# Connectors_ASCII.net
KiCad netlist of a schematic drawn in Altium Designer
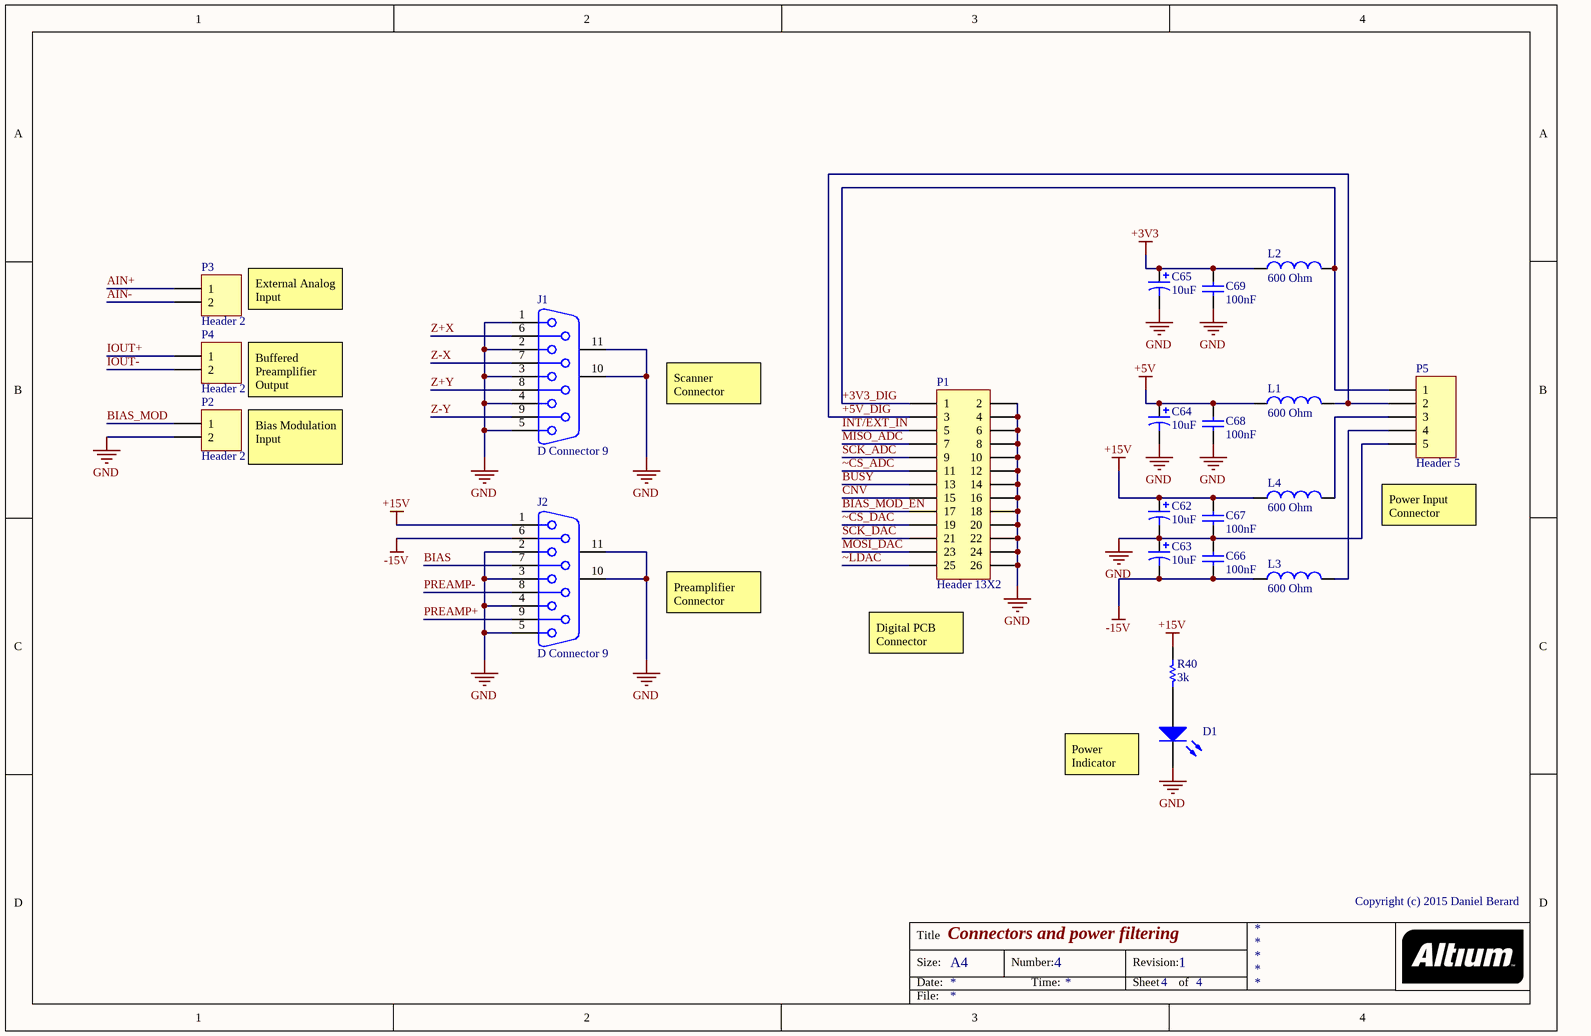
[diagram p0: Connectors_ASCII.SchDoc]

(export (version "E")
  (design (tool "Eeschema 10.0.6"))
  (components
    (comp (ref "C62")
      (value "10uF")
      (footprint "3528")
      (description "Polarized Capacitor (Radial)")
      (fields (field (name "PUBLISHER") "Altium Limited"))
      (libsource (lib "Miscellaneous Devices") (part "Cap Pol1"))
    )
    (comp (ref "C63")
      (value "10uF")
      (footprint "3528")
      (description "Polarized Capacitor (Radial)")
      (fields (field (name "PUBLISHER") "Altium Limited"))
      (libsource (lib "Miscellaneous Devices") (part "Cap Pol1"))
    )
    (comp (ref "C64")
      (value "10uF")
      (footprint "6-0805_N")
      (description "Polarized Capacitor (Radial)")
      (fields (field (name "PUBLISHER") "Altium Limited"))
      (libsource (lib "Miscellaneous Devices") (part "Cap Pol1"))
    )
    (comp (ref "C65")
      (value "10uF")
      (footprint "6-0805_N")
      (description "Polarized Capacitor (Radial)")
      (fields (field (name "PUBLISHER") "Altium Limited"))
      (libsource (lib "Miscellaneous Devices") (part "Cap Pol1"))
    )
    (comp (ref "C66")
      (value "100nF")
      (footprint "6-0805_N")
      (description "Capacitor")
      (fields (field (name "PUBLISHER") "Altium Limited"))
      (libsource (lib "Miscellaneous Devices") (part "Cap"))
    )
    (comp (ref "C67")
      (value "100nF")
      (footprint "6-0805_N")
      (description "Capacitor")
      (fields (field (name "PUBLISHER") "Altium Limited"))
      (libsource (lib "Miscellaneous Devices") (part "Cap"))
    )
    (comp (ref "C68")
      (value "100nF")
      (footprint "6-0805_N")
      (description "Capacitor")
      (fields (field (name "PUBLISHER") "Altium Limited"))
      (libsource (lib "Miscellaneous Devices") (part "Cap"))
    )
    (comp (ref "C69")
      (value "100nF")
      (footprint "6-0805_N")
      (description "Capacitor")
      (fields (field (name "PUBLISHER") "Altium Limited"))
      (libsource (lib "Miscellaneous Devices") (part "Cap"))
    )
    (comp (ref "D1")
      (value "~")
      (footprint "6-0805_N")
      (description "Typical INFRARED GaAs LED")
      (fields (field (name "PUBLISHER") "Altium Limited"))
      (libsource (lib "Miscellaneous Devices") (part "LED0"))
    )
    (comp (ref "J1")
      (value "D Connector 9")
      (footprint "DSUB1.385-2H9")
      (description "Receptacle Assembly, 9 Position, Right Angle")
      (fields (field (name "PUBLISHER") "Altium Limited"))
      (libsource (lib "Miscellaneous Connectors") (part "D Connector 9"))
    )
    (comp (ref "J2")
      (value "D Connector 9")
      (footprint "DSUB1.385-2H9")
      (description "Receptacle Assembly, 9 Position, Right Angle")
      (fields (field (name "PUBLISHER") "Altium Limited"))
      (libsource (lib "Miscellaneous Connectors") (part "D Connector 9"))
    )
    (comp (ref "L1")
      (value "600 Ohm")
      (footprint "6-0805_N")
      (description "Inductor")
      (fields (field (name "PUBLISHER") "Altium Limited"))
      (libsource (lib "Miscellaneous Devices") (part "Inductor"))
    )
    (comp (ref "L2")
      (value "600 Ohm")
      (footprint "6-0805_N")
      (description "Inductor")
      (fields (field (name "PUBLISHER") "Altium Limited"))
      (libsource (lib "Miscellaneous Devices") (part "Inductor"))
    )
    (comp (ref "L3")
      (value "600 Ohm")
      (footprint "6-0805_N")
      (description "Inductor")
      (fields (field (name "PUBLISHER") "Altium Limited"))
      (libsource (lib "Miscellaneous Devices") (part "Inductor"))
    )
    (comp (ref "L4")
      (value "600 Ohm")
      (footprint "6-0805_N")
      (description "Inductor")
      (fields (field (name "PUBLISHER") "Altium Limited"))
      (libsource (lib "Miscellaneous Devices") (part "Inductor"))
    )
    (comp (ref "P1")
      (value "Header 13X2")
      (footprint "HDR2X13")
      (description "Header, 13-Pin, Dual row")
      (fields (field (name "PUBLISHER") "Altium Limited"))
      (libsource (lib "Miscellaneous Connectors") (part "Header 13X2"))
    )
    (comp (ref "P2")
      (value "Header 2")
      (footprint "HDR1X2")
      (description "Header, 2-Pin")
      (fields (field (name "PUBLISHER") "Altium Limited"))
      (libsource (lib "Miscellaneous Connectors") (part "Header 2"))
    )
    (comp (ref "P3")
      (value "Header 2")
      (footprint "HDR1X2")
      (description "Header, 2-Pin")
      (fields (field (name "PUBLISHER") "Altium Limited"))
      (libsource (lib "Miscellaneous Connectors") (part "Header 2"))
    )
    (comp (ref "P4")
      (value "Header 2")
      (footprint "HDR1X2")
      (description "Header, 2-Pin")
      (fields (field (name "PUBLISHER") "Altium Limited"))
      (libsource (lib "Miscellaneous Connectors") (part "Header 2"))
    )
    (comp (ref "P5")
      (value "Header 5")
      (footprint "HDR1X5")
      (description "Header, 5-Pin")
      (fields (field (name "PUBLISHER") "Altium Limited"))
      (libsource (lib "Miscellaneous Connectors") (part "Header 5"))
    )
    (comp (ref "R40")
      (value "3k")
      (footprint "6-0805_N")
      (description "Resistor")
      (fields (field (name "PUBLISHER") "Altium Limited"))
      (libsource (lib "Miscellaneous Devices") (part "Res1"))
    )
  )
  (nets
    (net (code "1") (name "+3V3") (class "Default")
      (node (ref "C65") (pin "1") (pinfunction "1_1") (pintype "passive"))
      (node (ref "C69") (pin "1") (pinfunction "1_1") (pintype "passive"))
      (node (ref "L2") (pin "1") (pinfunction "1_1") (pintype "passive"))
    )
    (net (code "2") (name "+5V") (class "Default")
      (node (ref "C64") (pin "1") (pinfunction "1_1") (pintype "passive"))
      (node (ref "C68") (pin "1") (pinfunction "1_1") (pintype "passive"))
      (node (ref "L1") (pin "1") (pinfunction "1_1") (pintype "passive"))
    )
    (net (code "3") (name "+15V") (class "Default")
      (node (ref "C62") (pin "1") (pinfunction "1_1") (pintype "passive"))
      (node (ref "C67") (pin "1") (pinfunction "1_1") (pintype "passive"))
      (node (ref "J2") (pin "1") (pinfunction "1_1") (pintype "passive"))
      (node (ref "L4") (pin "1") (pinfunction "1_1") (pintype "passive"))
      (node (ref "R40") (pin "2") (pinfunction "2_2") (pintype "passive"))
    )
    (net (code "4") (name "-15V") (class "Default")
      (node (ref "C63") (pin "2") (pinfunction "2_2") (pintype "passive"))
      (node (ref "C66") (pin "2") (pinfunction "2_2") (pintype "passive"))
      (node (ref "J2") (pin "6") (pinfunction "6_6") (pintype "passive"))
      (node (ref "L3") (pin "1") (pinfunction "1_1") (pintype "passive"))
    )
    (net (code "5") (name "/+3V3_DIG") (class "Default")
      (node (ref "L2") (pin "2") (pinfunction "2_2") (pintype "passive"))
      (node (ref "P1") (pin "1") (pinfunction "1_1") (pintype "passive"))
      (node (ref "P5") (pin "1") (pinfunction "1_1") (pintype "passive"))
    )
    (net (code "6") (name "/+5V_DIG") (class "Default")
      (node (ref "L1") (pin "2") (pinfunction "2_2") (pintype "passive"))
      (node (ref "P1") (pin "3") (pinfunction "3_3") (pintype "passive"))
      (node (ref "P5") (pin "2") (pinfunction "2_2") (pintype "passive"))
    )
    (net (code "7") (name "/AIN+") (class "Default")
      (node (ref "P3") (pin "1") (pinfunction "1_1") (pintype "passive"))
    )
    (net (code "8") (name "/AIN-") (class "Default")
      (node (ref "P3") (pin "2") (pinfunction "2_2") (pintype "passive"))
    )
    (net (code "9") (name "/BIAS") (class "Default")
      (node (ref "J2") (pin "7") (pinfunction "7_7") (pintype "passive"))
    )
    (net (code "10") (name "/BIAS_MOD") (class "Default")
      (node (ref "P2") (pin "1") (pinfunction "1_1") (pintype "passive"))
    )
    (net (code "11") (name "/BIAS_MOD_EN") (class "Default")
      (node (ref "P1") (pin "17") (pinfunction "17_17") (pintype "passive"))
    )
    (net (code "12") (name "/BUSY") (class "Default")
      (node (ref "P1") (pin "13") (pinfunction "13_13") (pintype "passive"))
    )
    (net (code "13") (name "/CNV") (class "Default")
      (node (ref "P1") (pin "15") (pinfunction "15_15") (pintype "passive"))
    )
    (net (code "14") (name "/INT{slash}EXT_IN") (class "Default")
      (node (ref "P1") (pin "5") (pinfunction "5_5") (pintype "passive"))
    )
    (net (code "15") (name "/IOUT+") (class "Default")
      (node (ref "P4") (pin "1") (pinfunction "1_1") (pintype "passive"))
    )
    (net (code "16") (name "/IOUT-") (class "Default")
      (node (ref "P4") (pin "2") (pinfunction "2_2") (pintype "passive"))
    )
    (net (code "17") (name "/MISO_ADC") (class "Default")
      (node (ref "P1") (pin "7") (pinfunction "7_7") (pintype "passive"))
    )
    (net (code "18") (name "/MOSI_DAC") (class "Default")
      (node (ref "P1") (pin "23") (pinfunction "23_23") (pintype "passive"))
    )
    (net (code "19") (name "/PREAMP+") (class "Default")
      (node (ref "J2") (pin "9") (pinfunction "9_9") (pintype "passive"))
    )
    (net (code "20") (name "/PREAMP-") (class "Default")
      (node (ref "J2") (pin "8") (pinfunction "8_8") (pintype "passive"))
    )
    (net (code "21") (name "/SCK_ADC") (class "Default")
      (node (ref "P1") (pin "9") (pinfunction "9_9") (pintype "passive"))
    )
    (net (code "22") (name "/SCK_DAC") (class "Default")
      (node (ref "P1") (pin "21") (pinfunction "21_21") (pintype "passive"))
    )
    (net (code "23") (name "/Z+X") (class "Default")
      (node (ref "J1") (pin "6") (pinfunction "6_6") (pintype "passive"))
    )
    (net (code "24") (name "/Z+Y") (class "Default")
      (node (ref "J1") (pin "8") (pinfunction "8_8") (pintype "passive"))
    )
    (net (code "25") (name "/Z-X") (class "Default")
      (node (ref "J1") (pin "7") (pinfunction "7_7") (pintype "passive"))
    )
    (net (code "26") (name "/Z-Y") (class "Default")
      (node (ref "J1") (pin "9") (pinfunction "9_9") (pintype "passive"))
    )
    (net (code "27") (name "/~CS_ADC") (class "Default")
      (node (ref "P1") (pin "11") (pinfunction "11_11") (pintype "passive"))
    )
    (net (code "28") (name "/~CS_DAC") (class "Default")
      (node (ref "P1") (pin "19") (pinfunction "19_19") (pintype "passive"))
    )
    (net (code "29") (name "/~LDAC") (class "Default")
      (node (ref "P1") (pin "25") (pinfunction "25_25") (pintype "passive"))
    )
    (net (code "30") (name "GND") (class "Default")
      (node (ref "C62") (pin "2") (pinfunction "2_2") (pintype "passive"))
      (node (ref "C63") (pin "1") (pinfunction "1_1") (pintype "passive"))
      (node (ref "C64") (pin "2") (pinfunction "2_2") (pintype "passive"))
      (node (ref "C65") (pin "2") (pinfunction "2_2") (pintype "passive"))
      (node (ref "C66") (pin "1") (pinfunction "1_1") (pintype "passive"))
      (node (ref "C67") (pin "2") (pinfunction "2_2") (pintype "passive"))
      (node (ref "C68") (pin "2") (pinfunction "2_2") (pintype "passive"))
      (node (ref "C69") (pin "2") (pinfunction "2_2") (pintype "passive"))
      (node (ref "D1") (pin "2") (pinfunction "K_2") (pintype "passive"))
      (node (ref "J1") (pin "1") (pinfunction "1_1") (pintype "passive"))
      (node (ref "J1") (pin "10") (pinfunction "MH1_10") (pintype "passive"))
      (node (ref "J1") (pin "11") (pinfunction "MH2_11") (pintype "passive"))
      (node (ref "J1") (pin "2") (pinfunction "2_2") (pintype "passive"))
      (node (ref "J1") (pin "3") (pinfunction "3_3") (pintype "passive"))
      (node (ref "J1") (pin "4") (pinfunction "4_4") (pintype "passive"))
      (node (ref "J1") (pin "5") (pinfunction "5_5") (pintype "passive"))
      (node (ref "J2") (pin "10") (pinfunction "MH1_10") (pintype "passive"))
      (node (ref "J2") (pin "11") (pinfunction "MH2_11") (pintype "passive"))
      (node (ref "J2") (pin "2") (pinfunction "2_2") (pintype "passive"))
      (node (ref "J2") (pin "3") (pinfunction "3_3") (pintype "passive"))
      (node (ref "J2") (pin "4") (pinfunction "4_4") (pintype "passive"))
      (node (ref "J2") (pin "5") (pinfunction "5_5") (pintype "passive"))
      (node (ref "P1") (pin "10") (pinfunction "10_10") (pintype "passive"))
      (node (ref "P1") (pin "12") (pinfunction "12_12") (pintype "passive"))
      (node (ref "P1") (pin "14") (pinfunction "14_14") (pintype "passive"))
      (node (ref "P1") (pin "16") (pinfunction "16_16") (pintype "passive"))
      (node (ref "P1") (pin "18") (pinfunction "18_18") (pintype "passive"))
      (node (ref "P1") (pin "2") (pinfunction "2_2") (pintype "passive"))
      (node (ref "P1") (pin "20") (pinfunction "20_20") (pintype "passive"))
      (node (ref "P1") (pin "22") (pinfunction "22_22") (pintype "passive"))
      (node (ref "P1") (pin "24") (pinfunction "24_24") (pintype "passive"))
      (node (ref "P1") (pin "26") (pinfunction "26_26") (pintype "passive"))
      (node (ref "P1") (pin "4") (pinfunction "4_4") (pintype "passive"))
      (node (ref "P1") (pin "6") (pinfunction "6_6") (pintype "passive"))
      (node (ref "P1") (pin "8") (pinfunction "8_8") (pintype "passive"))
      (node (ref "P2") (pin "2") (pinfunction "2_2") (pintype "passive"))
      (node (ref "P5") (pin "5") (pinfunction "5_5") (pintype "passive"))
    )
    (net (code "31") (name "Net-(D1-A)") (class "Default")
      (node (ref "D1") (pin "1") (pinfunction "A_1") (pintype "passive"))
      (node (ref "R40") (pin "1") (pinfunction "1_1") (pintype "passive"))
    )
    (net (code "32") (name "Net-(L3-Pad2)") (class "Default")
      (node (ref "L3") (pin "2") (pinfunction "2_2") (pintype "passive"))
      (node (ref "P5") (pin "4") (pinfunction "4_4") (pintype "passive"))
    )
    (net (code "33") (name "Net-(L4-Pad2)") (class "Default")
      (node (ref "L4") (pin "2") (pinfunction "2_2") (pintype "passive"))
      (node (ref "P5") (pin "3") (pinfunction "3_3") (pintype "passive"))
    )
  )
)
